# hauptplatine.net
KiCad netlist of a schematic drawn in EAGLE
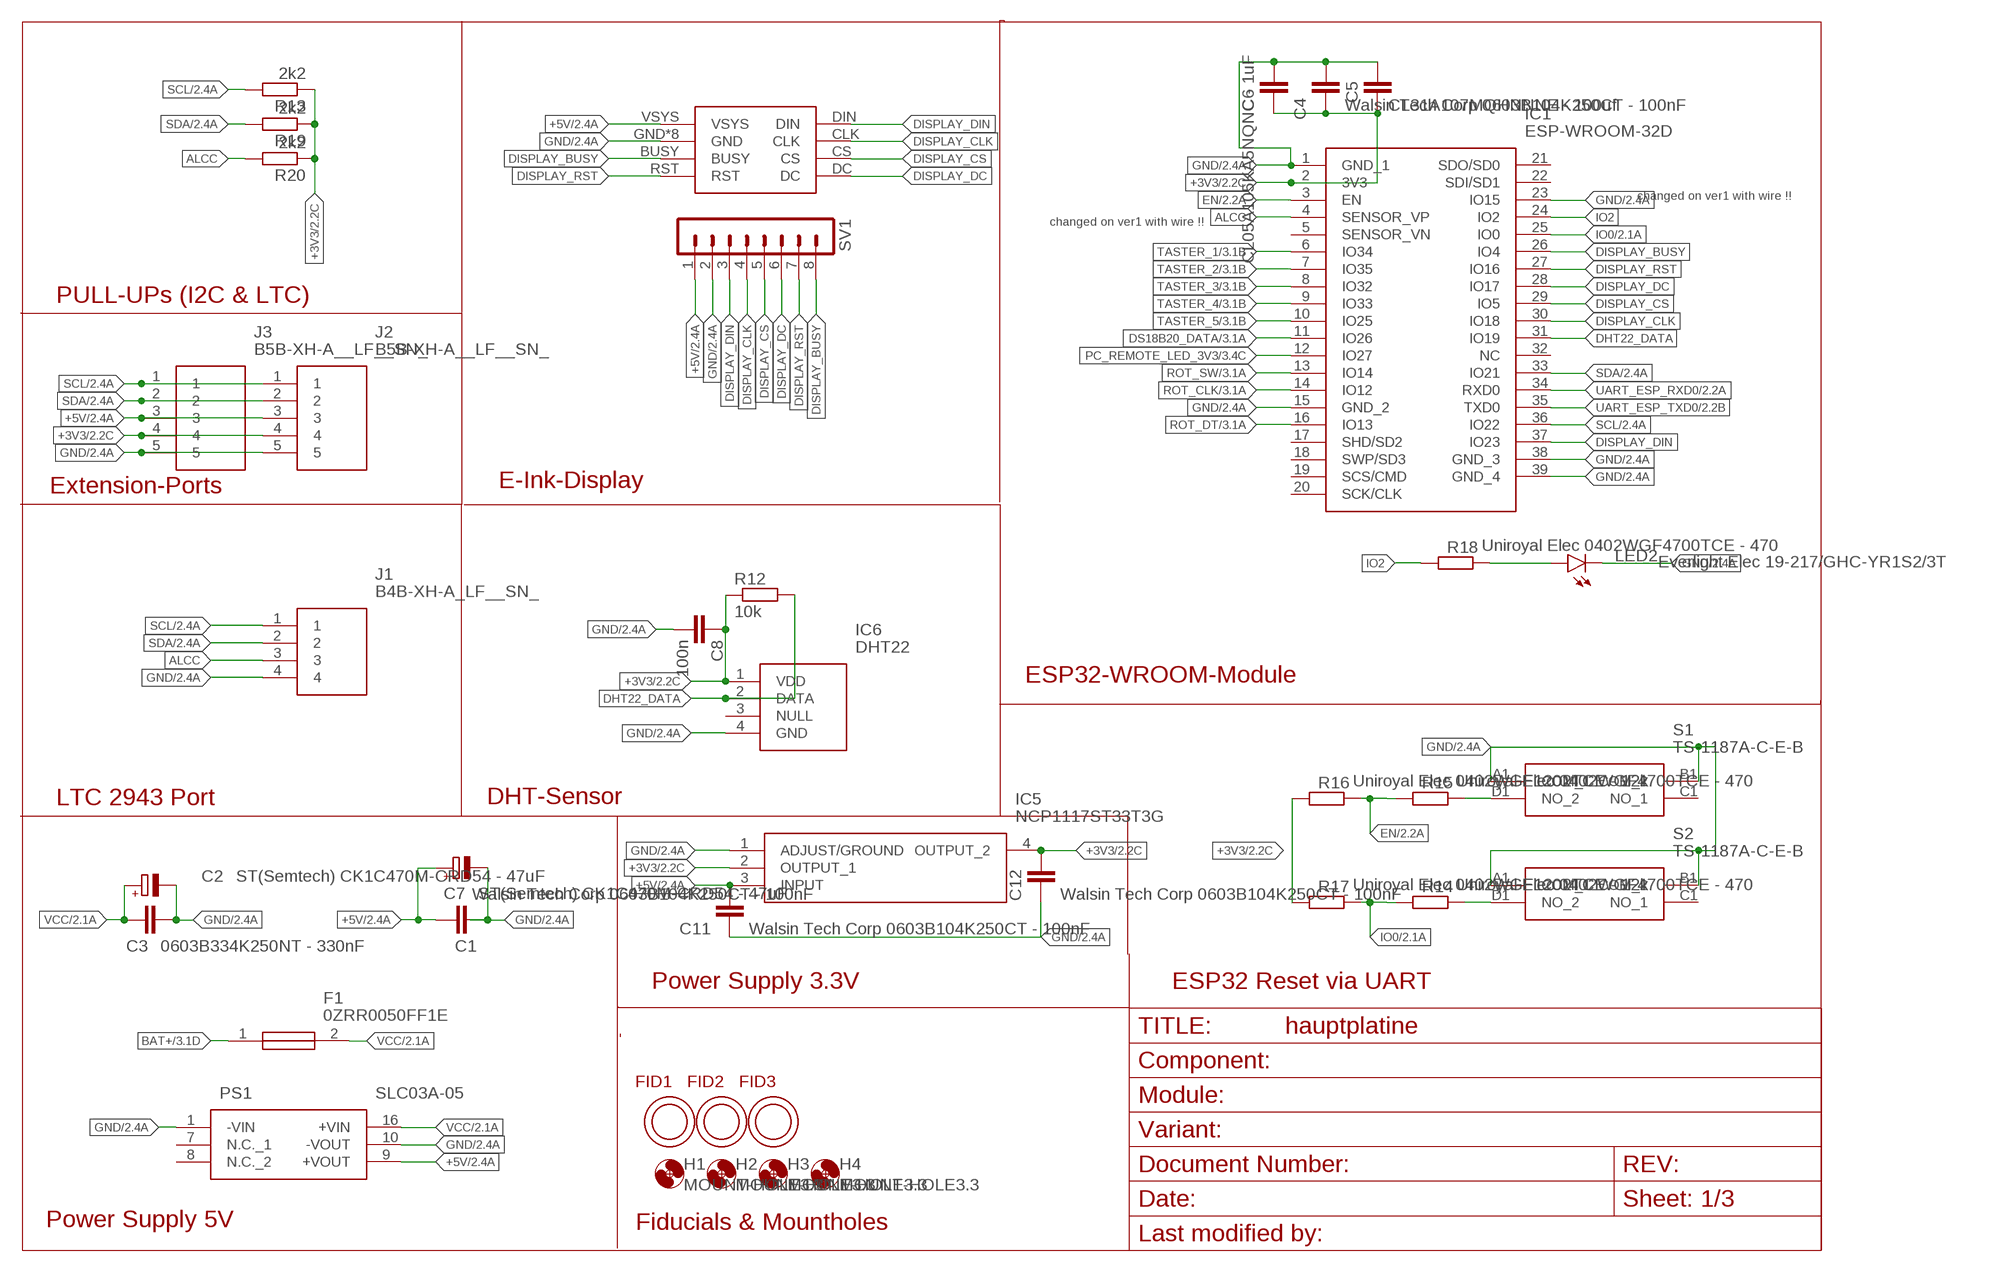
[diagram p0: schematic, sheet 1]
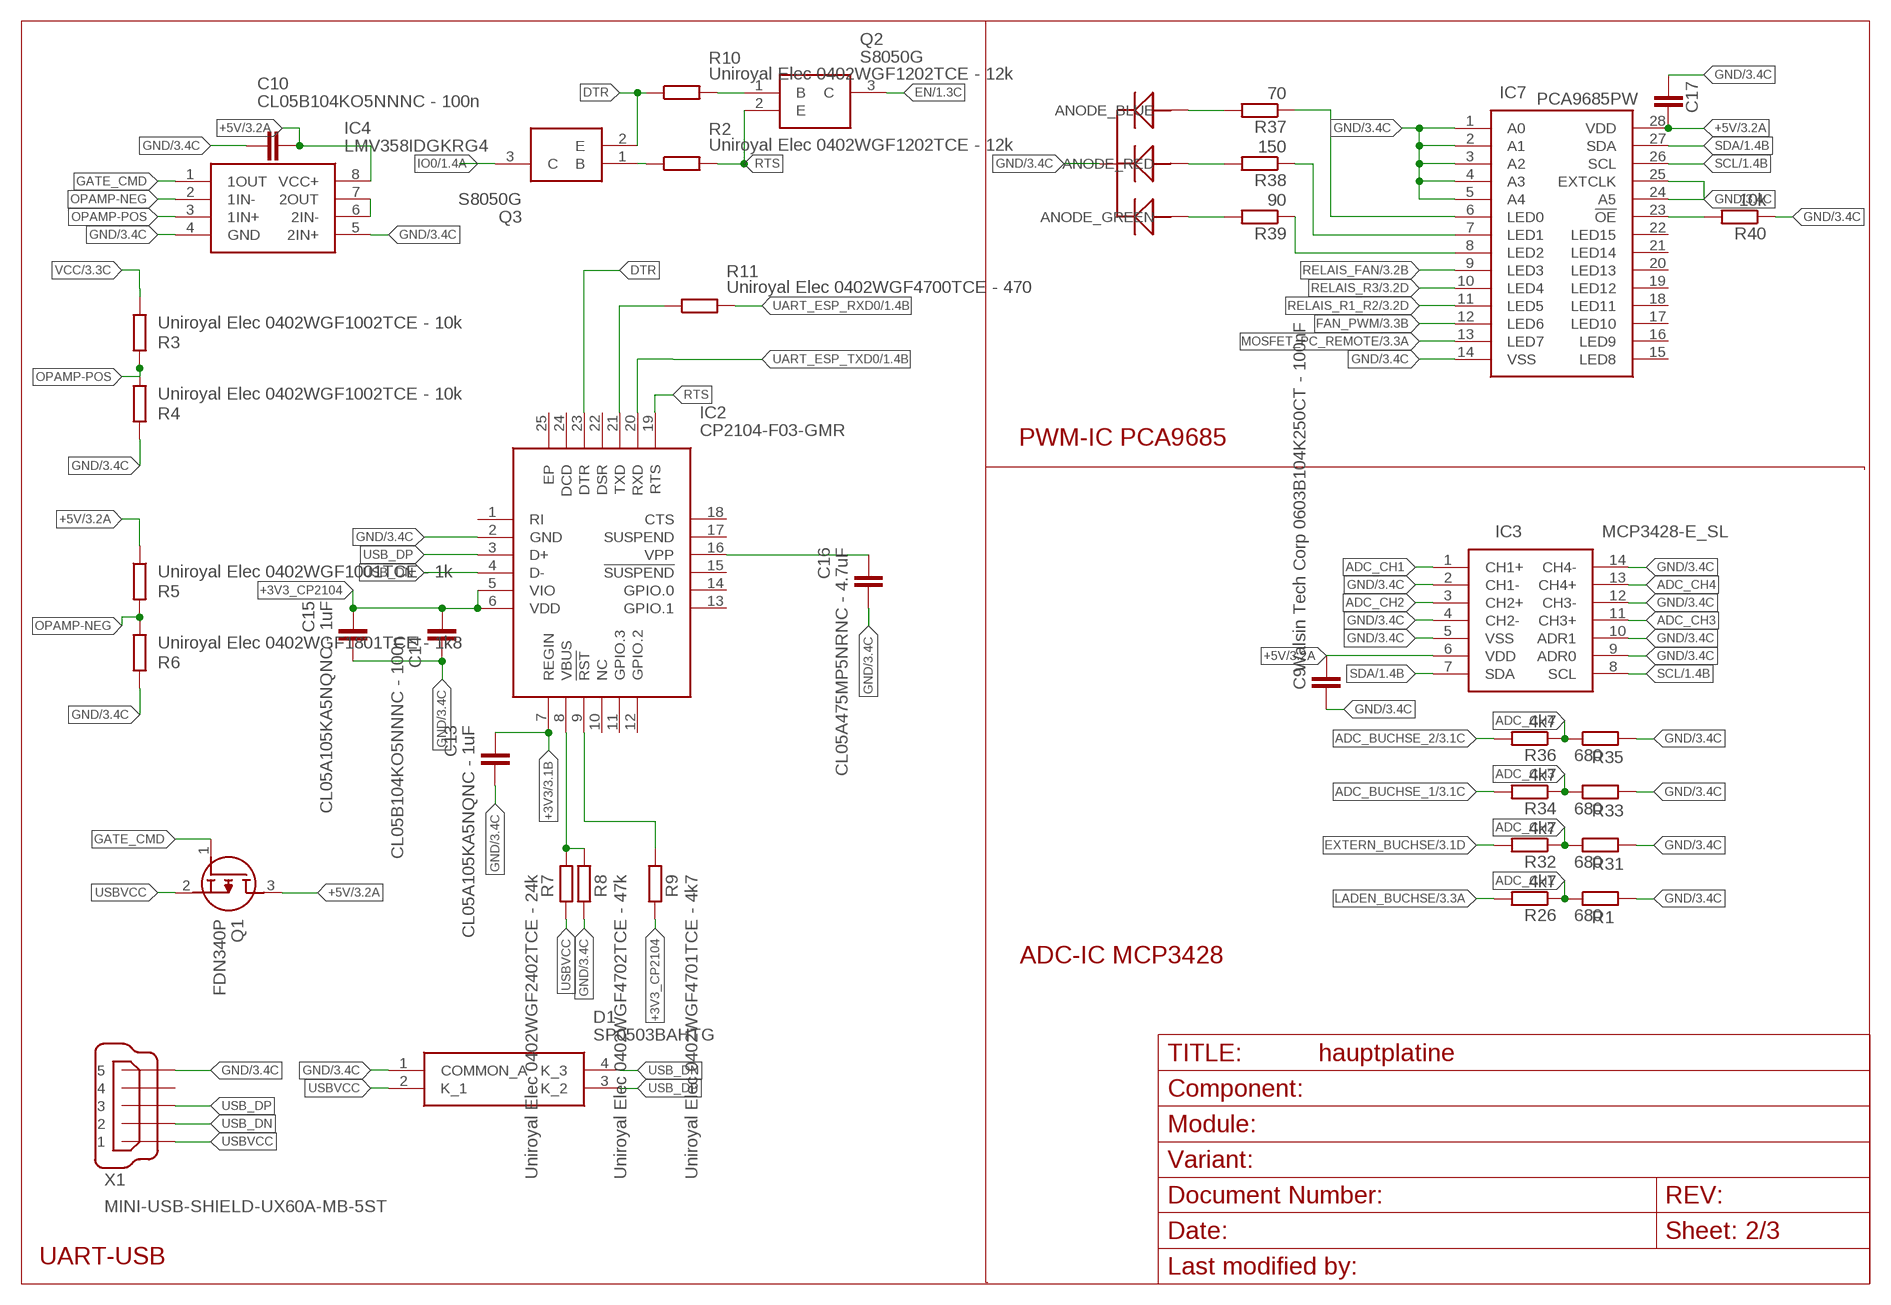
[diagram p1: schematic, sheet 2]
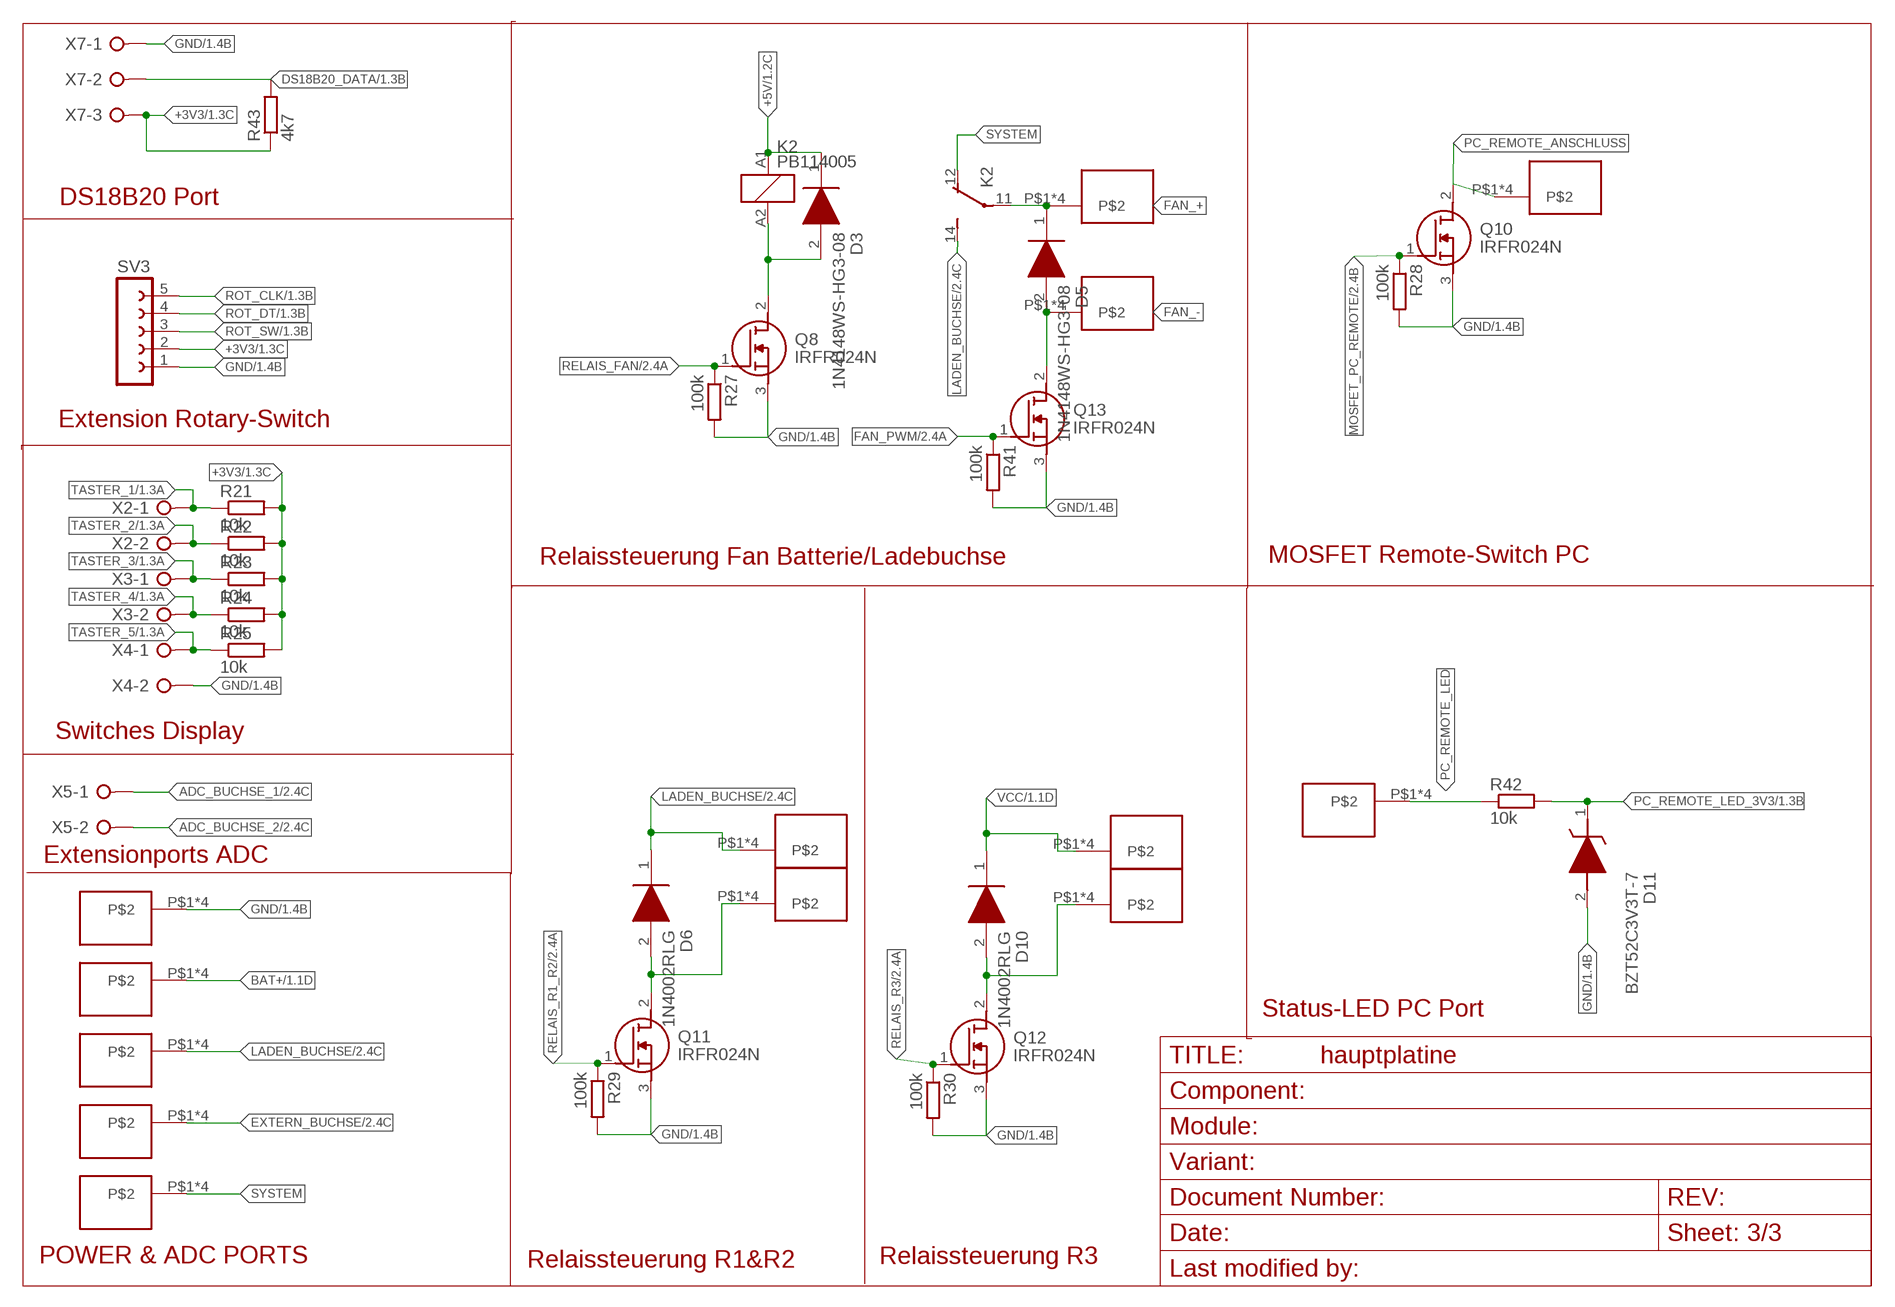
[diagram p2: schematic, sheet 3]

(export (version "E")
  (design (tool "Eeschema 10.0.6"))
  (components
    (comp (ref "C1")
      (value "Walsin Tech Corp 0603B104K250CT - 100nF")
      (footprint "eagle-import:C0603")
      (libsource (lib "eagle-import") (part "rcl_334_C-EUC0603"))
    )
    (comp (ref "C2")
      (value "ST(Semtech) CK1C470M-CRD54 - 47uF")
      (footprint "eagle-import:PANASONIC_C")
      (libsource (lib "eagle-import") (part "CPOL-EUC"))
    )
    (comp (ref "C3")
      (value "0603B334K250NT - 330nF")
      (footprint "eagle-import:C0603")
      (libsource (lib "eagle-import") (part "rcl_334_C-EUC0603"))
    )
    (comp (ref "C4")
      (value "Walsin Tech Corp 0603B104K250CT - 100nF")
      (footprint "eagle-import:C0603")
      (libsource (lib "eagle-import") (part "rcl_334_C-EUC0603"))
    )
    (comp (ref "C5")
      (value "CL31A107MQHNNNE - 100uf")
      (footprint "eagle-import:C1206")
      (libsource (lib "eagle-import") (part "rcl_334_C-EUC1206"))
    )
    (comp (ref "C6")
      (value "CL05A105KA5NQNC - 1uF")
      (footprint "eagle-import:C0402")
      (libsource (lib "eagle-import") (part "rcl_334_C-EUC0402"))
    )
    (comp (ref "C7")
      (value "ST(Semtech) CK1C470M-CRD54 - 47uF")
      (footprint "eagle-import:PANASONIC_C")
      (libsource (lib "eagle-import") (part "CPOL-EUC"))
    )
    (comp (ref "C8")
      (value "100n")
      (footprint "eagle-import:C1206")
      (libsource (lib "eagle-import") (part "C-EUC1206"))
    )
    (comp (ref "C11")
      (value "Walsin Tech Corp 0603B104K250CT - 100nF")
      (footprint "eagle-import:C0603")
      (libsource (lib "eagle-import") (part "rcl_334_C-EUC0603"))
    )
    (comp (ref "C12")
      (value "Walsin Tech Corp 0603B104K250CT - 100nF")
      (footprint "eagle-import:C0603")
      (libsource (lib "eagle-import") (part "rcl_334_C-EUC0603"))
    )
    (comp (ref "F1")
      (value "0ZRR0050FF1E")
      (footprint "eagle-import:0ZRR0050FF1E")
      (fields (field (name "MOUSER_PART_NUMBER") "530-0ZRR0050FF1E"))
      (libsource (lib "eagle-import") (part "0ZRR0050FF1E"))
    )
    (comp (ref "FID1")
      (value "OPEN-PNP-FIDUCIAL")
      (footprint "eagle-import:OPEN-PNP-FIDUCIAL")
      (libsource (lib "eagle-import") (part "OPEN-PNP-FIDUCIAL"))
    )
    (comp (ref "FID2")
      (value "OPEN-PNP-FIDUCIAL")
      (footprint "eagle-import:OPEN-PNP-FIDUCIAL")
      (libsource (lib "eagle-import") (part "OPEN-PNP-FIDUCIAL"))
    )
    (comp (ref "FID3")
      (value "OPEN-PNP-FIDUCIAL")
      (footprint "eagle-import:OPEN-PNP-FIDUCIAL")
      (libsource (lib "eagle-import") (part "OPEN-PNP-FIDUCIAL"))
    )
    (comp (ref "H1")
      (value "MOUNT-HOLE3.3")
      (footprint "eagle-import:3,3")
      (libsource (lib "eagle-import") (part "MOUNT-HOLE3.3"))
    )
    (comp (ref "H2")
      (value "MOUNT-HOLE3.3")
      (footprint "eagle-import:3,3")
      (libsource (lib "eagle-import") (part "MOUNT-HOLE3.3"))
    )
    (comp (ref "H3")
      (value "MOUNT-HOLE3.3")
      (footprint "eagle-import:3,3")
      (libsource (lib "eagle-import") (part "MOUNT-HOLE3.3"))
    )
    (comp (ref "H4")
      (value "MOUNT-HOLE3.3")
      (footprint "eagle-import:3,3")
      (libsource (lib "eagle-import") (part "MOUNT-HOLE3.3"))
    )
    (comp (ref "IC1")
      (value "ESP-WROOM-32D")
      (footprint "eagle-import:ESPWROOM32D")
      (fields (field (name "MOUSER_PART_NUMBER") "356-ESP-WROOM-32D"))
      (libsource (lib "eagle-import") (part "ESP-WROOM-32D"))
    )
    (comp (ref "IC5")
      (value "NCP1117ST33T3G")
      (footprint "eagle-import:SOT230P700X180-4N")
      (fields (field (name "MOUSER_PART_NUMBER") "863-NCP1117ST33T3G"))
      (libsource (lib "eagle-import") (part "NCP1117ST33T3G"))
    )
    (comp (ref "IC6")
      (value "DHT22")
      (footprint "eagle-import:DHT22")
      (libsource (lib "eagle-import") (part "DHT22"))
    )
    (comp (ref "J1")
      (value "B4B-XH-A_LF__SN_")
      (footprint "eagle-import:B4BXHALFSN")
      (fields (field (name "ARROW_PART_NUMBER") "B4B-XH-A(LF)(SN)"))
      (libsource (lib "eagle-import") (part "B4B-XH-A_LF__SN_"))
    )
    (comp (ref "J2")
      (value "B5B-XH-A__LF__SN_")
      (footprint "eagle-import:SHDR5W64P0X250_1X5_1490X575X70")
      (fields (field (name "MANUFACTURER_PART_NUMBER") "B5B-XH-A (LF)(SN)"))
      (libsource (lib "eagle-import") (part "B5B-XH-A__LF__SN_"))
    )
    (comp (ref "J3")
      (value "B5B-XH-A__LF__SN_")
      (footprint "eagle-import:SHDR5W64P0X250_1X5_1490X575X70")
      (fields (field (name "MANUFACTURER_PART_NUMBER") "B5B-XH-A (LF)(SN)"))
      (libsource (lib "eagle-import") (part "B5B-XH-A__LF__SN_"))
    )
    (comp (ref "LED2")
      (value "Everlight Elec 19-217/GHC-YR1S2/3T")
      (footprint "eagle-import:CHIPLED_0603")
      (libsource (lib "eagle-import") (part "LEDCHIPLED_0603"))
    )
    (comp (ref "PS1")
      (value "SLC03A-05")
      (footprint "eagle-import:SLC03A05")
      (fields (field (name "MOUSER_PART_NUMBER") "709-SLC03A-05"))
      (libsource (lib "eagle-import") (part "SLC03A-05"))
    )
    (comp (ref "R12")
      (value "10k")
      (footprint "eagle-import:R1206")
      (libsource (lib "eagle-import") (part "R-EU_R1206"))
    )
    (comp (ref "R13")
      (value "2k2")
      (footprint "eagle-import:R1206")
      (libsource (lib "eagle-import") (part "R-EU_R1206"))
    )
    (comp (ref "R14")
      (value "Uniroyal Elec 0402WGF4700TCE - 470")
      (footprint "eagle-import:R0402")
      (libsource (lib "eagle-import") (part "rcl_334_R-EU_R0402"))
    )
    (comp (ref "R15")
      (value "Uniroyal Elec 0402WGF4700TCE - 470")
      (footprint "eagle-import:R0402")
      (libsource (lib "eagle-import") (part "rcl_334_R-EU_R0402"))
    )
    (comp (ref "R16")
      (value "Uniroyal Elec 0402WGF1202TCE - 12k")
      (footprint "eagle-import:R0402")
      (libsource (lib "eagle-import") (part "rcl_334_R-EU_R0402"))
    )
    (comp (ref "R17")
      (value "Uniroyal Elec 0402WGF1202TCE - 12k")
      (footprint "eagle-import:R0402")
      (libsource (lib "eagle-import") (part "rcl_334_R-EU_R0402"))
    )
    (comp (ref "R18")
      (value "Uniroyal Elec 0402WGF4700TCE - 470")
      (footprint "eagle-import:R0402")
      (libsource (lib "eagle-import") (part "rcl_334_R-EU_R0402"))
    )
    (comp (ref "R19")
      (value "2k2")
      (footprint "eagle-import:R1206")
      (libsource (lib "eagle-import") (part "R-EU_R1206"))
    )
    (comp (ref "R20")
      (value "2k2")
      (footprint "eagle-import:R1206")
      (libsource (lib "eagle-import") (part "R-EU_R1206"))
    )
    (comp (ref "S1")
      (value "TS-1187A-C-E-B")
      (footprint "eagle-import:TS1187ACEB")
      (fields (field (name "MOUSER_PART_NUMBER") "611-PTS526SK15SMR2L"))
      (libsource (lib "eagle-import") (part "TS-1187A-C-E-B"))
    )
    (comp (ref "S2")
      (value "TS-1187A-C-E-B")
      (footprint "eagle-import:TS1187ACEB")
      (fields (field (name "MOUSER_PART_NUMBER") "611-PTS526SK15SMR2L"))
      (libsource (lib "eagle-import") (part "TS-1187A-C-E-B"))
    )
    (comp (ref "SV1")
      (value "MA08-1")
      (footprint "eagle-import:MA08-1")
      (libsource (lib "eagle-import") (part "MA08-1"))
    )
    (comp (ref "U$1")
      (value "PICO-EPAPER-2.9-V3")
      (footprint "eagle-import:PICO-EPAPER-2.9-V3")
      (libsource (lib "eagle-import") (part "PICO-EPAPER-2.9-V3"))
    )
    (comp (ref "C9")
      (value "Walsin Tech Corp 0603B104K250CT - 100nF")
      (footprint "eagle-import:C0603")
      (libsource (lib "eagle-import") (part "rcl_334_C-EUC0603"))
    )
    (comp (ref "C10")
      (value "CL05B104KO5NNNC - 100n")
      (footprint "eagle-import:C0402")
      (libsource (lib "eagle-import") (part "rcl_334_C-EUC0402"))
    )
    (comp (ref "C13")
      (value "CL05A105KA5NQNC - 1uF")
      (footprint "eagle-import:C0402")
      (libsource (lib "eagle-import") (part "rcl_334_C-EUC0402"))
    )
    (comp (ref "C14")
      (value "CL05B104KO5NNNC - 100n")
      (footprint "eagle-import:C0402")
      (libsource (lib "eagle-import") (part "rcl_334_C-EUC0402"))
    )
    (comp (ref "C15")
      (value "CL05A105KA5NQNC - 1uF")
      (footprint "eagle-import:C0402")
      (libsource (lib "eagle-import") (part "rcl_334_C-EUC0402"))
    )
    (comp (ref "C16")
      (value "CL05A475MP5NRNC - 4.7uF")
      (footprint "eagle-import:C0402")
      (libsource (lib "eagle-import") (part "rcl_334_C-EUC0402"))
    )
    (comp (ref "C17")
      (value "Walsin Tech Corp 0603B104K250CT - 100nF")
      (footprint "eagle-import:C0603")
      (libsource (lib "eagle-import") (part "rcl_334_C-EUC0603"))
    )
    (comp (ref "D1")
      (value "SP0503BAHTG")
      (footprint "eagle-import:SP0503BAHTG")
      (fields (field (name "MOUSER_PART_NUMBER") "576-SP0503BAHTG"))
      (libsource (lib "eagle-import") (part "SP0503BAHTG"))
    )
    (comp (ref "IC2")
      (value "CP2104-F03-GMR")
      (footprint "eagle-import:QFN50P400X400X80-25N")
      (fields (field (name "MOUSER_PART_NUMBER") "634-CP2104-F03-GMR"))
      (libsource (lib "eagle-import") (part "CP2104-F03-GMR"))
    )
    (comp (ref "IC3")
      (value "MCP3428-E_SL")
      (footprint "eagle-import:SOIC127P600X175-14N")
      (fields
        (field (name "ARROW_PART_NUMBER") "MCP3428-E/SL")
        (field (name "MOUSER_PART_NUMBER") "579-MCP3428E/SL")
      )
      (libsource (lib "eagle-import") (part "MCP3428-E_SL"))
    )
    (comp (ref "IC4")
      (value "LMV358IDGKRG4")
      (footprint "eagle-import:SOP65P490X110-8N")
      (fields (field (name "MOUSER_PART_NUMBER") "595-LMV358IDGKRG4"))
      (libsource (lib "eagle-import") (part "LMV358IDGKRG4"))
    )
    (comp (ref "IC7")
      (value "PCA9685PW")
      (footprint "eagle-import:SOP65P640X110-28N")
      (libsource (lib "eagle-import") (part "PCA9685PW"))
    )
    (comp (ref "Q1")
      (value "FDN340P")
      (footprint "eagle-import:SOT95P237X112-3N")
      (fields (field (name "MOUSER_PART_NUMBER") "512-FDN340P"))
      (libsource (lib "eagle-import") (part "FDN340P"))
    )
    (comp (ref "Q2")
      (value "S8050G")
      (footprint "eagle-import:SOT95P240X110-3N")
      (libsource (lib "eagle-import") (part "S8050G"))
    )
    (comp (ref "Q3")
      (value "S8050G")
      (footprint "eagle-import:SOT95P240X110-3N")
      (libsource (lib "eagle-import") (part "S8050G"))
    )
    (comp (ref "R1")
      (value "680")
      (footprint "eagle-import:R1206")
      (libsource (lib "eagle-import") (part "R-EU_R1206"))
    )
    (comp (ref "R2")
      (value "Uniroyal Elec 0402WGF1202TCE - 12k")
      (footprint "eagle-import:R0402")
      (libsource (lib "eagle-import") (part "rcl_334_R-EU_R0402"))
    )
    (comp (ref "R3")
      (value "Uniroyal Elec 0402WGF1002TCE - 10k")
      (footprint "eagle-import:R0402")
      (libsource (lib "eagle-import") (part "rcl_334_R-EU_R0402"))
    )
    (comp (ref "R4")
      (value "Uniroyal Elec 0402WGF1002TCE - 10k")
      (footprint "eagle-import:R0402")
      (libsource (lib "eagle-import") (part "rcl_334_R-EU_R0402"))
    )
    (comp (ref "R5")
      (value "Uniroyal Elec 0402WGF1001TCE - 1k")
      (footprint "eagle-import:R0402")
      (libsource (lib "eagle-import") (part "rcl_334_R-EU_R0402"))
    )
    (comp (ref "R6")
      (value "Uniroyal Elec 0402WGF1801TCE - 1k8")
      (footprint "eagle-import:R0402")
      (libsource (lib "eagle-import") (part "rcl_334_R-EU_R0402"))
    )
    (comp (ref "R7")
      (value "Uniroyal Elec 0402WGF2402TCE - 24k")
      (footprint "eagle-import:R0402")
      (libsource (lib "eagle-import") (part "rcl_334_R-EU_R0402"))
    )
    (comp (ref "R8")
      (value "Uniroyal Elec 0402WGF4702TCE - 47k")
      (footprint "eagle-import:R0402")
      (libsource (lib "eagle-import") (part "rcl_334_R-EU_R0402"))
    )
    (comp (ref "R9")
      (value "Uniroyal Elec 0402WGF4701TCE - 4k7")
      (footprint "eagle-import:R0402")
      (libsource (lib "eagle-import") (part "rcl_334_R-EU_R0402"))
    )
    (comp (ref "R10")
      (value "Uniroyal Elec 0402WGF1202TCE - 12k")
      (footprint "eagle-import:R0402")
      (libsource (lib "eagle-import") (part "rcl_334_R-EU_R0402"))
    )
    (comp (ref "R11")
      (value "Uniroyal Elec 0402WGF4700TCE - 470")
      (footprint "eagle-import:R0402")
      (libsource (lib "eagle-import") (part "rcl_334_R-EU_R0402"))
    )
    (comp (ref "R26")
      (value "4k7")
      (footprint "eagle-import:R1206")
      (libsource (lib "eagle-import") (part "R-EU_R1206"))
    )
    (comp (ref "R31")
      (value "680")
      (footprint "eagle-import:R1206")
      (libsource (lib "eagle-import") (part "R-EU_R1206"))
    )
    (comp (ref "R32")
      (value "4k7")
      (footprint "eagle-import:R1206")
      (libsource (lib "eagle-import") (part "R-EU_R1206"))
    )
    (comp (ref "R33")
      (value "680")
      (footprint "eagle-import:R1206")
      (libsource (lib "eagle-import") (part "R-EU_R1206"))
    )
    (comp (ref "R34")
      (value "4k7")
      (footprint "eagle-import:R1206")
      (libsource (lib "eagle-import") (part "R-EU_R1206"))
    )
    (comp (ref "R35")
      (value "680")
      (footprint "eagle-import:R1206")
      (libsource (lib "eagle-import") (part "R-EU_R1206"))
    )
    (comp (ref "R36")
      (value "4k7")
      (footprint "eagle-import:R1206")
      (libsource (lib "eagle-import") (part "R-EU_R1206"))
    )
    (comp (ref "R37")
      (value "70")
      (footprint "eagle-import:R1206")
      (libsource (lib "eagle-import") (part "R-EU_R1206"))
    )
    (comp (ref "R38")
      (value "150")
      (footprint "eagle-import:R1206")
      (libsource (lib "eagle-import") (part "R-EU_R1206"))
    )
    (comp (ref "R39")
      (value "90")
      (footprint "eagle-import:R1206")
      (libsource (lib "eagle-import") (part "R-EU_R1206"))
    )
    (comp (ref "R40")
      (value "10k")
      (footprint "eagle-import:R1206")
      (libsource (lib "eagle-import") (part "R-EU_R1206"))
    )
    (comp (ref "U$12")
      (value "RG_LED_5MM")
      (footprint "eagle-import:RGB_LED_5MM")
      (libsource (lib "eagle-import") (part "RG_LED_5MM"))
    )
    (comp (ref "X1")
      (value "MINI-USB-SHIELD-UX60A-MB-5ST")
      (footprint "eagle-import:UX60A-MB-5ST")
      (libsource (lib "eagle-import") (part "MINI-USB-SHIELD-UX60A-MB-5ST"))
    )
    (comp (ref "D3")
      (value "1N4148WS-HG3-08")
      (footprint "eagle-import:SOD2713X115N")
      (fields (field (name "MOUSER_PART_NUMBER") "78-1N4148WS-HG3-08"))
      (libsource (lib "eagle-import") (part "1N4148WS-HG3-08"))
    )
    (comp (ref "D5")
      (value "1N4148WS-HG3-08")
      (footprint "eagle-import:SOD2713X115N")
      (fields (field (name "MOUSER_PART_NUMBER") "78-1N4148WS-HG3-08"))
      (libsource (lib "eagle-import") (part "1N4148WS-HG3-08"))
    )
    (comp (ref "D6")
      (value "1N4002RLG")
      (footprint "eagle-import:DIOAD1405W86L465D235")
      (fields (field (name "MOUSER_PART_NUMBER") "863-1N4002RLG"))
      (libsource (lib "eagle-import") (part "1N4002RLG"))
    )
    (comp (ref "D10")
      (value "1N4002RLG")
      (footprint "eagle-import:DIOAD1405W86L465D235")
      (fields (field (name "MOUSER_PART_NUMBER") "863-1N4002RLG"))
      (libsource (lib "eagle-import") (part "1N4002RLG"))
    )
    (comp (ref "D11")
      (value "BZT52C3V3T-7")
      (footprint "eagle-import:SODFL1608X65N")
      (fields (field (name "MOUSER_PART_NUMBER") "621-BZT52C3V3T-7"))
      (libsource (lib "eagle-import") (part "BZT52C3V3T-7"))
    )
    (comp (ref "K2")
      (value "PB114005")
      (footprint "eagle-import:PB")
      (fields (field (name "MF") "TYCO ELECTRONICS") (field (name "MPN") "PB114006"))
      (libsource (lib "eagle-import") (part "PB?141006"))
    )
    (comp (ref "Q8")
      (value "IRFR024N")
      (footprint "eagle-import:IRFR024TRPBFBE3")
      (fields
        (field (name "ARROW_PART_NUMBER") "IRFR024TRPBF-BE3")
        (field (name "MOUSER_PART_NUMBER") "78-IRFR024TRPBF-BE3")
      )
      (libsource (lib "eagle-import") (part "IRFR024TRPBF-BE3"))
    )
    (comp (ref "Q10")
      (value "IRFR024N")
      (footprint "eagle-import:IRFR024TRPBFBE3")
      (fields
        (field (name "ARROW_PART_NUMBER") "IRFR024TRPBF-BE3")
        (field (name "MOUSER_PART_NUMBER") "78-IRFR024TRPBF-BE3")
      )
      (libsource (lib "eagle-import") (part "IRFR024TRPBF-BE3"))
    )
    (comp (ref "Q11")
      (value "IRFR024N")
      (footprint "eagle-import:IRFR024TRPBFBE3")
      (fields
        (field (name "ARROW_PART_NUMBER") "IRFR024TRPBF-BE3")
        (field (name "MOUSER_PART_NUMBER") "78-IRFR024TRPBF-BE3")
      )
      (libsource (lib "eagle-import") (part "IRFR024TRPBF-BE3"))
    )
    (comp (ref "Q12")
      (value "IRFR024N")
      (footprint "eagle-import:IRFR024TRPBFBE3")
      (fields
        (field (name "ARROW_PART_NUMBER") "IRFR024TRPBF-BE3")
        (field (name "MOUSER_PART_NUMBER") "78-IRFR024TRPBF-BE3")
      )
      (libsource (lib "eagle-import") (part "IRFR024TRPBF-BE3"))
    )
    (comp (ref "Q13")
      (value "IRFR024N")
      (footprint "eagle-import:IRFR024TRPBFBE3")
      (fields
        (field (name "ARROW_PART_NUMBER") "IRFR024TRPBF-BE3")
        (field (name "MOUSER_PART_NUMBER") "78-IRFR024TRPBF-BE3")
      )
      (libsource (lib "eagle-import") (part "IRFR024TRPBF-BE3"))
    )
    (comp (ref "R21")
      (value "10k")
      (footprint "eagle-import:R0805")
      (libsource (lib "eagle-import") (part "R-EU_R0805"))
    )
    (comp (ref "R22")
      (value "10k")
      (footprint "eagle-import:R0805")
      (libsource (lib "eagle-import") (part "R-EU_R0805"))
    )
    (comp (ref "R23")
      (value "10k")
      (footprint "eagle-import:R0805")
      (libsource (lib "eagle-import") (part "R-EU_R0805"))
    )
    (comp (ref "R24")
      (value "10k")
      (footprint "eagle-import:R0805")
      (libsource (lib "eagle-import") (part "R-EU_R0805"))
    )
    (comp (ref "R25")
      (value "10k")
      (footprint "eagle-import:R0805")
      (libsource (lib "eagle-import") (part "R-EU_R0805"))
    )
    (comp (ref "R27")
      (value "100k")
      (footprint "eagle-import:R1206")
      (libsource (lib "eagle-import") (part "R-EU_R1206"))
    )
    (comp (ref "R28")
      (value "100k")
      (footprint "eagle-import:R1206")
      (libsource (lib "eagle-import") (part "R-EU_R1206"))
    )
    (comp (ref "R29")
      (value "100k")
      (footprint "eagle-import:R1206")
      (libsource (lib "eagle-import") (part "R-EU_R1206"))
    )
    (comp (ref "R30")
      (value "100k")
      (footprint "eagle-import:R1206")
      (libsource (lib "eagle-import") (part "R-EU_R1206"))
    )
    (comp (ref "R41")
      (value "100k")
      (footprint "eagle-import:R1206")
      (libsource (lib "eagle-import") (part "R-EU_R1206"))
    )
    (comp (ref "R42")
      (value "10k")
      (footprint "eagle-import:R1206")
      (libsource (lib "eagle-import") (part "R-EU_R1206"))
    )
    (comp (ref "R43")
      (value "4k7")
      (footprint "eagle-import:R0805")
      (libsource (lib "eagle-import") (part "R-EU_R0805"))
    )
    (comp (ref "SV3")
      (value "FE05-1")
      (footprint "eagle-import:FE05-1")
      (libsource (lib "eagle-import") (part "FE05-1"))
    )
    (comp (ref "U$2")
      (value "WE-REDCUBE-74650173")
      (footprint "eagle-import:WE-REDCUBE-74650173")
      (libsource (lib "eagle-import") (part "WE-REDCUBE-74650173"))
    )
    (comp (ref "U$17")
      (value "WE-REDCUBE-74650173")
      (footprint "eagle-import:WE-REDCUBE-74650173")
      (libsource (lib "eagle-import") (part "WE-REDCUBE-74650173"))
    )
    (comp (ref "U$18")
      (value "WE-REDCUBE-74650173")
      (footprint "eagle-import:WE-REDCUBE-74650173")
      (libsource (lib "eagle-import") (part "WE-REDCUBE-74650173"))
    )
    (comp (ref "U$19")
      (value "WE-REDCUBE-74650173")
      (footprint "eagle-import:WE-REDCUBE-74650173")
      (libsource (lib "eagle-import") (part "WE-REDCUBE-74650173"))
    )
    (comp (ref "U$20")
      (value "WE-REDCUBE-74650173")
      (footprint "eagle-import:WE-REDCUBE-74650173")
      (libsource (lib "eagle-import") (part "WE-REDCUBE-74650173"))
    )
    (comp (ref "U$21")
      (value "WE-REDCUBE-74650173")
      (footprint "eagle-import:WE-REDCUBE-74650173")
      (libsource (lib "eagle-import") (part "WE-REDCUBE-74650173"))
    )
    (comp (ref "U$22")
      (value "WE-REDCUBE-74650173")
      (footprint "eagle-import:WE-REDCUBE-74650173")
      (libsource (lib "eagle-import") (part "WE-REDCUBE-74650173"))
    )
    (comp (ref "U$23")
      (value "WE-REDCUBE-74650173")
      (footprint "eagle-import:WE-REDCUBE-74650173")
      (libsource (lib "eagle-import") (part "WE-REDCUBE-74650173"))
    )
    (comp (ref "U$24")
      (value "WE-REDCUBE-74650173")
      (footprint "eagle-import:WE-REDCUBE-74650173")
      (libsource (lib "eagle-import") (part "WE-REDCUBE-74650173"))
    )
    (comp (ref "U$25")
      (value "WE-REDCUBE-74650173")
      (footprint "eagle-import:WE-REDCUBE-74650173")
      (libsource (lib "eagle-import") (part "WE-REDCUBE-74650173"))
    )
    (comp (ref "U$26")
      (value "WE-REDCUBE-74650173")
      (footprint "eagle-import:WE-REDCUBE-74650173")
      (libsource (lib "eagle-import") (part "WE-REDCUBE-74650173"))
    )
    (comp (ref "U$27")
      (value "WE-REDCUBE-74650173")
      (footprint "eagle-import:WE-REDCUBE-74650173")
      (libsource (lib "eagle-import") (part "WE-REDCUBE-74650173"))
    )
    (comp (ref "U$28")
      (value "WE-REDCUBE-74650173")
      (footprint "eagle-import:WE-REDCUBE-74650173")
      (libsource (lib "eagle-import") (part "WE-REDCUBE-74650173"))
    )
    (comp (ref "X2")
      (value "W237-02P")
      (footprint "eagle-import:W237-132")
      (libsource (lib "eagle-import") (part "W237-02P"))
    )
    (comp (ref "X3")
      (value "W237-02P")
      (footprint "eagle-import:W237-132")
      (libsource (lib "eagle-import") (part "W237-02P"))
    )
    (comp (ref "X4")
      (value "W237-02P")
      (footprint "eagle-import:W237-132")
      (libsource (lib "eagle-import") (part "W237-02P"))
    )
    (comp (ref "X5")
      (value "W237-02P")
      (footprint "eagle-import:W237-132")
      (libsource (lib "eagle-import") (part "W237-02P"))
    )
    (comp (ref "X7")
      (value "W237-3E")
      (footprint "eagle-import:W237-3E")
      (libsource (lib "eagle-import") (part "W237-3E"))
    )
  )
  (nets
    (net (code "1") (name "+3V3") (class "Default")
      (node (ref "C12") (pin "2") (pinfunction "2_2") (pintype "passive"))
      (node (ref "C13") (pin "2") (pinfunction "2_2") (pintype "passive"))
      (node (ref "C4") (pin "1") (pinfunction "1_1") (pintype "passive"))
      (node (ref "C5") (pin "2") (pinfunction "2_2") (pintype "passive"))
      (node (ref "C6") (pin "1") (pinfunction "1_1") (pintype "passive"))
      (node (ref "C8") (pin "1") (pinfunction "1_1") (pintype "passive"))
      (node (ref "IC1") (pin "2") (pinfunction "3V3_2") (pintype "bidirectional"))
      (node (ref "IC2") (pin "7") (pinfunction "REGIN_7") (pintype "bidirectional"))
      (node (ref "IC5") (pin "2") (pinfunction "OUTPUT_1_2") (pintype "bidirectional"))
      (node (ref "IC5") (pin "4") (pinfunction "OUTPUT_2_4") (pintype "bidirectional"))
      (node (ref "IC6") (pin "1") (pinfunction "VDD_1") (pintype "bidirectional"))
      (node (ref "J2") (pin "4") (pinfunction "4_4") (pintype "bidirectional"))
      (node (ref "J3") (pin "4") (pinfunction "4_4") (pintype "bidirectional"))
      (node (ref "R12") (pin "1") (pinfunction "1_1") (pintype "passive"))
      (node (ref "R13") (pin "1") (pinfunction "1_1") (pintype "passive"))
      (node (ref "R16") (pin "1") (pinfunction "1_1") (pintype "passive"))
      (node (ref "R17") (pin "1") (pinfunction "1_1") (pintype "passive"))
      (node (ref "R19") (pin "1") (pinfunction "1_1") (pintype "passive"))
      (node (ref "R20") (pin "1") (pinfunction "1_1") (pintype "passive"))
      (node (ref "R21") (pin "2") (pinfunction "2_2") (pintype "passive"))
      (node (ref "R22") (pin "2") (pinfunction "2_2") (pintype "passive"))
      (node (ref "R23") (pin "2") (pinfunction "2_2") (pintype "passive"))
      (node (ref "R24") (pin "2") (pinfunction "2_2") (pintype "passive"))
      (node (ref "R25") (pin "2") (pinfunction "2_2") (pintype "passive"))
      (node (ref "R43") (pin "1") (pinfunction "1_1") (pintype "passive"))
      (node (ref "SV3") (pin "2") (pinfunction "2_2") (pintype "passive"))
      (node (ref "X7") (pin "3") (pinfunction "KL_3") (pintype "passive"))
    )
    (net (code "2") (name "+3V3_CP2104") (class "Default")
      (node (ref "C14") (pin "2") (pinfunction "2_2") (pintype "passive"))
      (node (ref "C15") (pin "2") (pinfunction "2_2") (pintype "passive"))
      (node (ref "IC2") (pin "5") (pinfunction "VIO_5") (pintype "bidirectional"))
      (node (ref "IC2") (pin "6") (pinfunction "VDD_6") (pintype "bidirectional"))
      (node (ref "R9") (pin "2") (pinfunction "2_2") (pintype "passive"))
    )
    (net (code "3") (name "+5V") (class "Default")
      (node (ref "C1") (pin "1") (pinfunction "1_1") (pintype "passive"))
      (node (ref "C10") (pin "2") (pinfunction "2_2") (pintype "passive"))
      (node (ref "C11") (pin "2") (pinfunction "2_2") (pintype "passive"))
      (node (ref "C17") (pin "1") (pinfunction "1_1") (pintype "passive"))
      (node (ref "C7") (pin "+") (pinfunction "+_+") (pintype "passive"))
      (node (ref "C9") (pin "2") (pinfunction "2_2") (pintype "passive"))
      (node (ref "D3") (pin "1") (pinfunction "K_1") (pintype "bidirectional"))
      (node (ref "IC3") (pin "6") (pinfunction "VDD_6") (pintype "bidirectional"))
      (node (ref "IC4") (pin "8") (pinfunction "VCC+_8") (pintype "bidirectional"))
      (node (ref "IC5") (pin "3") (pinfunction "INPUT_3") (pintype "bidirectional"))
      (node (ref "IC7") (pin "28") (pinfunction "VDD_28") (pintype "bidirectional"))
      (node (ref "J2") (pin "3") (pinfunction "3_3") (pintype "bidirectional"))
      (node (ref "J3") (pin "3") (pinfunction "3_3") (pintype "bidirectional"))
      (node (ref "K2") (pin "A1") (pinfunction "1_A1") (pintype "passive"))
      (node (ref "PS1") (pin "9") (pinfunction "+VOUT_9") (pintype "bidirectional"))
      (node (ref "Q1") (pin "3") (pinfunction "D_3") (pintype "bidirectional"))
      (node (ref "R5") (pin "1") (pinfunction "1_1") (pintype "passive"))
      (node (ref "SV1") (pin "1") (pinfunction "1_1") (pintype "passive"))
      (node (ref "U$1") (pin "VSYS") (pinfunction "VSYS_VSYS") (pintype "bidirectional"))
    )
    (net (code "4") (name "ADC_BUCHSE_1") (class "Default")
      (node (ref "R34") (pin "2") (pinfunction "2_2") (pintype "passive"))
      (node (ref "X5") (pin "1") (pinfunction "KL_1") (pintype "passive"))
    )
    (net (code "5") (name "ADC_BUCHSE_2") (class "Default")
      (node (ref "R36") (pin "2") (pinfunction "2_2") (pintype "passive"))
      (node (ref "X5") (pin "2") (pinfunction "KL_2") (pintype "passive"))
    )
    (net (code "6") (name "ADC_CH1") (class "Default")
      (node (ref "IC3") (pin "1") (pinfunction "CH1+_1") (pintype "bidirectional"))
      (node (ref "R1") (pin "1") (pinfunction "1_1") (pintype "passive"))
      (node (ref "R26") (pin "1") (pinfunction "1_1") (pintype "passive"))
    )
    (net (code "7") (name "ADC_CH2") (class "Default")
      (node (ref "IC3") (pin "3") (pinfunction "CH2+_3") (pintype "bidirectional"))
      (node (ref "R31") (pin "1") (pinfunction "1_1") (pintype "passive"))
      (node (ref "R32") (pin "1") (pinfunction "1_1") (pintype "passive"))
    )
    (net (code "8") (name "ADC_CH3") (class "Default")
      (node (ref "IC3") (pin "11") (pinfunction "CH3+_11") (pintype "bidirectional"))
      (node (ref "R33") (pin "1") (pinfunction "1_1") (pintype "passive"))
      (node (ref "R34") (pin "1") (pinfunction "1_1") (pintype "passive"))
    )
    (net (code "9") (name "ADC_CH4") (class "Default")
      (node (ref "IC3") (pin "13") (pinfunction "CH4+_13") (pintype "bidirectional"))
      (node (ref "R35") (pin "1") (pinfunction "1_1") (pintype "passive"))
      (node (ref "R36") (pin "1") (pinfunction "1_1") (pintype "passive"))
    )
    (net (code "10") (name "ALCC") (class "Default")
      (node (ref "IC1") (pin "4") (pinfunction "SENSOR_VP_4") (pintype "bidirectional"))
      (node (ref "J1") (pin "3") (pinfunction "3_3") (pintype "bidirectional"))
      (node (ref "R20") (pin "2") (pinfunction "2_2") (pintype "passive"))
    )
    (net (code "11") (name "BAT+") (class "Default")
      (node (ref "F1") (pin "1") (pinfunction "1_1") (pintype "bidirectional"))
      (node (ref "U$17") (pin "P$1") (pinfunction "P$2_P$1") (pintype "bidirectional"))
      (node (ref "U$17") (pin "P$2") (pinfunction "P$2_P$2") (pintype "bidirectional"))
      (node (ref "U$17") (pin "P$3") (pinfunction "P$2_P$3") (pintype "bidirectional"))
      (node (ref "U$17") (pin "P$4") (pinfunction "P$2_P$4") (pintype "bidirectional"))
    )
    (net (code "12") (name "DHT22_DATA") (class "Default")
      (node (ref "IC1") (pin "31") (pinfunction "IO19_31") (pintype "bidirectional"))
      (node (ref "IC6") (pin "2") (pinfunction "DATA_2") (pintype "bidirectional"))
      (node (ref "R12") (pin "2") (pinfunction "2_2") (pintype "passive"))
    )
    (net (code "13") (name "DISPLAY_BUSY") (class "Default")
      (node (ref "IC1") (pin "26") (pinfunction "IO4_26") (pintype "bidirectional"))
      (node (ref "SV1") (pin "8") (pinfunction "8_8") (pintype "passive"))
      (node (ref "U$1") (pin "BUSY") (pinfunction "BUSY_BUSY") (pintype "bidirectional"))
    )
    (net (code "14") (name "DISPLAY_CLK") (class "Default")
      (node (ref "IC1") (pin "30") (pinfunction "IO18_30") (pintype "bidirectional"))
      (node (ref "SV1") (pin "4") (pinfunction "4_4") (pintype "passive"))
      (node (ref "U$1") (pin "CLK") (pinfunction "CLK_CLK") (pintype "bidirectional"))
    )
    (net (code "15") (name "DISPLAY_CS") (class "Default")
      (node (ref "IC1") (pin "29") (pinfunction "IO5_29") (pintype "bidirectional"))
      (node (ref "SV1") (pin "5") (pinfunction "5_5") (pintype "passive"))
      (node (ref "U$1") (pin "CS") (pinfunction "CS_CS") (pintype "bidirectional"))
    )
    (net (code "16") (name "DISPLAY_DC") (class "Default")
      (node (ref "IC1") (pin "28") (pinfunction "IO17_28") (pintype "bidirectional"))
      (node (ref "SV1") (pin "6") (pinfunction "6_6") (pintype "passive"))
      (node (ref "U$1") (pin "DC") (pinfunction "DC_DC") (pintype "bidirectional"))
    )
    (net (code "17") (name "DISPLAY_DIN") (class "Default")
      (node (ref "IC1") (pin "37") (pinfunction "IO23_37") (pintype "bidirectional"))
      (node (ref "SV1") (pin "3") (pinfunction "3_3") (pintype "passive"))
      (node (ref "U$1") (pin "DIN") (pinfunction "DIN_DIN") (pintype "bidirectional"))
    )
    (net (code "18") (name "DISPLAY_RST") (class "Default")
      (node (ref "IC1") (pin "27") (pinfunction "IO16_27") (pintype "bidirectional"))
      (node (ref "SV1") (pin "7") (pinfunction "7_7") (pintype "passive"))
      (node (ref "U$1") (pin "RST") (pinfunction "RST_RST") (pintype "bidirectional"))
    )
    (net (code "19") (name "DS18B20_DATA") (class "Default")
      (node (ref "IC1") (pin "11") (pinfunction "IO26_11") (pintype "bidirectional"))
      (node (ref "R43") (pin "2") (pinfunction "2_2") (pintype "passive"))
      (node (ref "X7") (pin "2") (pinfunction "KL_2") (pintype "passive"))
    )
    (net (code "20") (name "DTR") (class "Default")
      (node (ref "IC2") (pin "23") (pinfunction "DTR_23") (pintype "bidirectional"))
      (node (ref "Q3") (pin "2") (pinfunction "E_2") (pintype "bidirectional"))
      (node (ref "R10") (pin "1") (pinfunction "1_1") (pintype "passive"))
    )
    (net (code "21") (name "EN") (class "Default")
      (node (ref "IC1") (pin "3") (pinfunction "EN_3") (pintype "bidirectional"))
      (node (ref "Q2") (pin "3") (pinfunction "C_3") (pintype "bidirectional"))
      (node (ref "R15") (pin "1") (pinfunction "1_1") (pintype "passive"))
      (node (ref "R16") (pin "2") (pinfunction "2_2") (pintype "passive"))
    )
    (net (code "22") (name "EXTERN_BUCHSE") (class "Default")
      (node (ref "R32") (pin "2") (pinfunction "2_2") (pintype "passive"))
      (node (ref "U$19") (pin "P$1") (pinfunction "P$2_P$1") (pintype "bidirectional"))
      (node (ref "U$19") (pin "P$2") (pinfunction "P$2_P$2") (pintype "bidirectional"))
      (node (ref "U$19") (pin "P$3") (pinfunction "P$2_P$3") (pintype "bidirectional"))
      (node (ref "U$19") (pin "P$4") (pinfunction "P$2_P$4") (pintype "bidirectional"))
    )
    (net (code "23") (name "FAN_+") (class "Default")
      (node (ref "D5") (pin "1") (pinfunction "K_1") (pintype "bidirectional"))
      (node (ref "K2") (pin "11") (pinfunction "P_11") (pintype "passive"))
      (node (ref "U$24") (pin "P$1") (pinfunction "P$2_P$1") (pintype "bidirectional"))
      (node (ref "U$24") (pin "P$2") (pinfunction "P$2_P$2") (pintype "bidirectional"))
      (node (ref "U$24") (pin "P$3") (pinfunction "P$2_P$3") (pintype "bidirectional"))
      (node (ref "U$24") (pin "P$4") (pinfunction "P$2_P$4") (pintype "bidirectional"))
    )
    (net (code "24") (name "FAN_-") (class "Default")
      (node (ref "D5") (pin "2") (pinfunction "A_2") (pintype "bidirectional"))
      (node (ref "Q13") (pin "2") (pinfunction "D_2") (pintype "bidirectional"))
      (node (ref "U$27") (pin "P$1") (pinfunction "P$2_P$1") (pintype "bidirectional"))
      (node (ref "U$27") (pin "P$2") (pinfunction "P$2_P$2") (pintype "bidirectional"))
      (node (ref "U$27") (pin "P$3") (pinfunction "P$2_P$3") (pintype "bidirectional"))
      (node (ref "U$27") (pin "P$4") (pinfunction "P$2_P$4") (pintype "bidirectional"))
    )
    (net (code "25") (name "FAN_PWM") (class "Default")
      (node (ref "IC7") (pin "12") (pinfunction "LED6_12") (pintype "bidirectional"))
      (node (ref "Q13") (pin "1") (pinfunction "G_1") (pintype "bidirectional"))
      (node (ref "R41") (pin "1") (pinfunction "1_1") (pintype "passive"))
    )
    (net (code "26") (name "GATE_CMD") (class "Default")
      (node (ref "IC4") (pin "1") (pinfunction "1OUT_1") (pintype "bidirectional"))
      (node (ref "Q1") (pin "1") (pinfunction "G_1") (pintype "bidirectional"))
    )
    (net (code "27") (name "GND") (class "Default")
      (node (ref "C1") (pin "2") (pinfunction "2_2") (pintype "passive"))
      (node (ref "C10") (pin "1") (pinfunction "1_1") (pintype "passive"))
      (node (ref "C11") (pin "1") (pinfunction "1_1") (pintype "passive"))
      (node (ref "C12") (pin "1") (pinfunction "1_1") (pintype "passive"))
      (node (ref "C13") (pin "1") (pinfunction "1_1") (pintype "passive"))
      (node (ref "C14") (pin "1") (pinfunction "1_1") (pintype "passive"))
      (node (ref "C15") (pin "1") (pinfunction "1_1") (pintype "passive"))
      (node (ref "C16") (pin "1") (pinfunction "1_1") (pintype "passive"))
      (node (ref "C17") (pin "2") (pinfunction "2_2") (pintype "passive"))
      (node (ref "C2") (pin "-") (pinfunction "-_-") (pintype "passive"))
      (node (ref "C3") (pin "1") (pinfunction "1_1") (pintype "passive"))
      (node (ref "C4") (pin "2") (pinfunction "2_2") (pintype "passive"))
      (node (ref "C5") (pin "1") (pinfunction "1_1") (pintype "passive"))
      (node (ref "C6") (pin "2") (pinfunction "2_2") (pintype "passive"))
      (node (ref "C7") (pin "-") (pinfunction "-_-") (pintype "passive"))
      (node (ref "C8") (pin "2") (pinfunction "2_2") (pintype "passive"))
      (node (ref "C9") (pin "1") (pinfunction "1_1") (pintype "passive"))
      (node (ref "D1") (pin "1") (pinfunction "COMMON_A_1") (pintype "bidirectional"))
      (node (ref "D11") (pin "2") (pinfunction "A_2") (pintype "bidirectional"))
      (node (ref "IC1") (pin "1") (pinfunction "GND_1_1") (pintype "bidirectional"))
      (node (ref "IC1") (pin "15") (pinfunction "GND_2_15") (pintype "bidirectional"))
      (node (ref "IC1") (pin "23") (pinfunction "IO15_23") (pintype "bidirectional"))
      (node (ref "IC1") (pin "38") (pinfunction "GND_3_38") (pintype "bidirectional"))
      (node (ref "IC1") (pin "39") (pinfunction "GND_4_39") (pintype "bidirectional"))
      (node (ref "IC2") (pin "2") (pinfunction "GND_2") (pintype "bidirectional"))
      (node (ref "IC3") (pin "10") (pinfunction "ADR1_10") (pintype "bidirectional"))
      (node (ref "IC3") (pin "12") (pinfunction "CH3-_12") (pintype "bidirectional"))
      (node (ref "IC3") (pin "14") (pinfunction "CH4-_14") (pintype "bidirectional"))
      (node (ref "IC3") (pin "2") (pinfunction "CH1-_2") (pintype "bidirectional"))
      (node (ref "IC3") (pin "4") (pinfunction "CH2-_4") (pintype "bidirectional"))
      (node (ref "IC3") (pin "5") (pinfunction "VSS_5") (pintype "bidirectional"))
      (node (ref "IC3") (pin "9") (pinfunction "ADR0_9") (pintype "bidirectional"))
      (node (ref "IC4") (pin "4") (pinfunction "GND_4") (pintype "bidirectional"))
      (node (ref "IC4") (pin "5") (pinfunction "2IN+_5") (pintype "bidirectional"))
      (node (ref "IC5") (pin "1") (pinfunction "ADJUST/GROUND_1") (pintype "bidirectional"))
      (node (ref "IC6") (pin "4") (pinfunction "GND_4") (pintype "bidirectional"))
      (node (ref "IC7") (pin "1") (pinfunction "A0_1") (pintype "bidirectional"))
      (node (ref "IC7") (pin "14") (pinfunction "VSS_14") (pintype "bidirectional"))
      (node (ref "IC7") (pin "2") (pinfunction "A1_2") (pintype "bidirectional"))
      (node (ref "IC7") (pin "24") (pinfunction "A5_24") (pintype "bidirectional"))
      (node (ref "IC7") (pin "25") (pinfunction "EXTCLK_25") (pintype "bidirectional"))
      (node (ref "IC7") (pin "3") (pinfunction "A2_3") (pintype "bidirectional"))
      (node (ref "IC7") (pin "4") (pinfunction "A3_4") (pintype "bidirectional"))
      (node (ref "IC7") (pin "5") (pinfunction "A4_5") (pintype "bidirectional"))
      (node (ref "J1") (pin "4") (pinfunction "4_4") (pintype "bidirectional"))
      (node (ref "J2") (pin "5") (pinfunction "5_5") (pintype "bidirectional"))
      (node (ref "J3") (pin "5") (pinfunction "5_5") (pintype "bidirectional"))
      (node (ref "LED2") (pin "C") (pinfunction "C_C") (pintype "passive"))
      (node (ref "PS1") (pin "1") (pinfunction "-VIN_1") (pintype "bidirectional"))
      (node (ref "PS1") (pin "10") (pinfunction "-VOUT_10") (pintype "bidirectional"))
      (node (ref "Q10") (pin "3") (pinfunction "S_3") (pintype "bidirectional"))
      (node (ref "Q11") (pin "3") (pinfunction "S_3") (pintype "bidirectional"))
      (node (ref "Q12") (pin "3") (pinfunction "S_3") (pintype "bidirectional"))
      (node (ref "Q13") (pin "3") (pinfunction "S_3") (pintype "bidirectional"))
      (node (ref "Q8") (pin "3") (pinfunction "S_3") (pintype "bidirectional"))
      (node (ref "R1") (pin "2") (pinfunction "2_2") (pintype "passive"))
      (node (ref "R27") (pin "2") (pinfunction "2_2") (pintype "passive"))
      (node (ref "R28") (pin "2") (pinfunction "2_2") (pintype "passive"))
      (node (ref "R29") (pin "2") (pinfunction "2_2") (pintype "passive"))
      (node (ref "R30") (pin "2") (pinfunction "2_2") (pintype "passive"))
      (node (ref "R31") (pin "2") (pinfunction "2_2") (pintype "passive"))
      (node (ref "R33") (pin "2") (pinfunction "2_2") (pintype "passive"))
      (node (ref "R35") (pin "2") (pinfunction "2_2") (pintype "passive"))
      (node (ref "R4") (pin "2") (pinfunction "2_2") (pintype "passive"))
      (node (ref "R40") (pin "1") (pinfunction "1_1") (pintype "passive"))
      (node (ref "R41") (pin "2") (pinfunction "2_2") (pintype "passive"))
      (node (ref "R6") (pin "2") (pinfunction "2_2") (pintype "passive"))
      (node (ref "R8") (pin "2") (pinfunction "2_2") (pintype "passive"))
      (node (ref "S1") (pin "A1") (pinfunction "COM_1_A1") (pintype "bidirectional"))
      (node (ref "S1") (pin "B1") (pinfunction "COM_2_B1") (pintype "bidirectional"))
      (node (ref "S2") (pin "A1") (pinfunction "COM_1_A1") (pintype "bidirectional"))
      (node (ref "S2") (pin "B1") (pinfunction "COM_2_B1") (pintype "bidirectional"))
      (node (ref "SV1") (pin "2") (pinfunction "2_2") (pintype "passive"))
      (node (ref "SV3") (pin "1") (pinfunction "1_1") (pintype "passive"))
      (node (ref "U$1") (pin "GND") (pinfunction "GND_GND") (pintype "bidirectional"))
      (node (ref "U$1") (pin "GND1") (pinfunction "GND_GND1") (pintype "bidirectional"))
      (node (ref "U$1") (pin "GND2") (pinfunction "GND_GND2") (pintype "bidirectional"))
      (node (ref "U$1") (pin "GND3") (pinfunction "GND_GND3") (pintype "bidirectional"))
      (node (ref "U$1") (pin "GND4") (pinfunction "GND_GND4") (pintype "bidirectional"))
      (node (ref "U$1") (pin "GND5") (pinfunction "GND_GND5") (pintype "bidirectional"))
      (node (ref "U$1") (pin "GND6") (pinfunction "GND_GND6") (pintype "bidirectional"))
      (node (ref "U$1") (pin "GND7") (pinfunction "GND_GND7") (pintype "bidirectional"))
      (node (ref "U$12") (pin "CATHODE") (pinfunction "CATHODE_CATHODE") (pintype "bidirectional"))
      (node (ref "U$2") (pin "P$1") (pinfunction "P$2_P$1") (pintype "bidirectional"))
      (node (ref "U$2") (pin "P$2") (pinfunction "P$2_P$2") (pintype "bidirectional"))
      (node (ref "U$2") (pin "P$3") (pinfunction "P$2_P$3") (pintype "bidirectional"))
      (node (ref "U$2") (pin "P$4") (pinfunction "P$2_P$4") (pintype "bidirectional"))
      (node (ref "X1") (pin "5") (pinfunction "5_5") (pintype "input"))
      (node (ref "X4") (pin "2") (pinfunction "KL_2") (pintype "passive"))
      (node (ref "X7") (pin "1") (pinfunction "KL_1") (pintype "passive"))
    )
    (net (code "28") (name "IO0") (class "Default")
      (node (ref "IC1") (pin "25") (pinfunction "IO0_25") (pintype "bidirectional"))
      (node (ref "Q3") (pin "3") (pinfunction "C_3") (pintype "bidirectional"))
      (node (ref "R14") (pin "1") (pinfunction "1_1") (pintype "passive"))
      (node (ref "R17") (pin "2") (pinfunction "2_2") (pintype "passive"))
    )
    (net (code "29") (name "IO2") (class "Default")
      (node (ref "IC1") (pin "24") (pinfunction "IO2_24") (pintype "bidirectional"))
      (node (ref "R18") (pin "1") (pinfunction "1_1") (pintype "passive"))
    )
    (net (code "30") (name "LADEN_BUCHSE") (class "Default")
      (node (ref "D6") (pin "1") (pinfunction "K_1") (pintype "bidirectional"))
      (node (ref "K2") (pin "14") (pinfunction "S_14") (pintype "passive"))
      (node (ref "R26") (pin "2") (pinfunction "2_2") (pintype "passive"))
      (node (ref "U$18") (pin "P$1") (pinfunction "P$2_P$1") (pintype "bidirectional"))
      (node (ref "U$18") (pin "P$2") (pinfunction "P$2_P$2") (pintype "bidirectional"))
      (node (ref "U$18") (pin "P$3") (pinfunction "P$2_P$3") (pintype "bidirectional"))
      (node (ref "U$18") (pin "P$4") (pinfunction "P$2_P$4") (pintype "bidirectional"))
      (node (ref "U$21") (pin "P$1") (pinfunction "P$2_P$1") (pintype "bidirectional"))
      (node (ref "U$21") (pin "P$2") (pinfunction "P$2_P$2") (pintype "bidirectional"))
      (node (ref "U$21") (pin "P$3") (pinfunction "P$2_P$3") (pintype "bidirectional"))
      (node (ref "U$21") (pin "P$4") (pinfunction "P$2_P$4") (pintype "bidirectional"))
    )
    (net (code "31") (name "MOSFET_PC_REMOTE") (class "Default")
      (node (ref "IC7") (pin "13") (pinfunction "LED7_13") (pintype "bidirectional"))
      (node (ref "Q10") (pin "1") (pinfunction "G_1") (pintype "bidirectional"))
      (node (ref "R28") (pin "1") (pinfunction "1_1") (pintype "passive"))
    )
    (net (code "32") (name "Net-(D3-A)") (class "Default")
      (node (ref "D3") (pin "2") (pinfunction "A_2") (pintype "bidirectional"))
      (node (ref "K2") (pin "A2") (pinfunction "2_A2") (pintype "passive"))
      (node (ref "Q8") (pin "2") (pinfunction "D_2") (pintype "bidirectional"))
    )
    (net (code "33") (name "Net-(D6-A)") (class "Default")
      (node (ref "D6") (pin "2") (pinfunction "A_2") (pintype "bidirectional"))
      (node (ref "Q11") (pin "2") (pinfunction "D_2") (pintype "bidirectional"))
      (node (ref "U$20") (pin "P$1") (pinfunction "P$2_P$1") (pintype "bidirectional"))
      (node (ref "U$20") (pin "P$2") (pinfunction "P$2_P$2") (pintype "bidirectional"))
      (node (ref "U$20") (pin "P$3") (pinfunction "P$2_P$3") (pintype "bidirectional"))
      (node (ref "U$20") (pin "P$4") (pinfunction "P$2_P$4") (pintype "bidirectional"))
    )
    (net (code "34") (name "Net-(D10-A)") (class "Default")
      (node (ref "D10") (pin "2") (pinfunction "A_2") (pintype "bidirectional"))
      (node (ref "Q12") (pin "2") (pinfunction "D_2") (pintype "bidirectional"))
      (node (ref "U$22") (pin "P$1") (pinfunction "P$2_P$1") (pintype "bidirectional"))
      (node (ref "U$22") (pin "P$2") (pinfunction "P$2_P$2") (pintype "bidirectional"))
      (node (ref "U$22") (pin "P$3") (pinfunction "P$2_P$3") (pintype "bidirectional"))
      (node (ref "U$22") (pin "P$4") (pinfunction "P$2_P$4") (pintype "bidirectional"))
    )
    (net (code "35") (name "Net-(IC2-TXD)") (class "Default")
      (node (ref "IC2") (pin "21") (pinfunction "TXD_21") (pintype "bidirectional"))
      (node (ref "R11") (pin "1") (pinfunction "1_1") (pintype "passive"))
    )
    (net (code "36") (name "Net-(IC2-VBUS)") (class "Default")
      (node (ref "IC2") (pin "8") (pinfunction "VBUS_8") (pintype "bidirectional"))
      (node (ref "R7") (pin "1") (pinfunction "1_1") (pintype "passive"))
      (node (ref "R8") (pin "1") (pinfunction "1_1") (pintype "passive"))
    )
    (net (code "37") (name "Net-(IC2-VPP)") (class "Default")
      (node (ref "C16") (pin "2") (pinfunction "2_2") (pintype "passive"))
      (node (ref "IC2") (pin "16") (pinfunction "VPP_16") (pintype "bidirectional"))
    )
    (net (code "38") (name "Net-(IC2-~{RST})") (class "Default")
      (node (ref "IC2") (pin "9") (pinfunction "~{RST}_9") (pintype "bidirectional"))
      (node (ref "R9") (pin "1") (pinfunction "1_1") (pintype "passive"))
    )
    (net (code "39") (name "Net-(IC4-2IN-)") (class "Default")
      (node (ref "IC4") (pin "6") (pinfunction "2IN-_6") (pintype "bidirectional"))
      (node (ref "IC4") (pin "7") (pinfunction "2OUT_7") (pintype "bidirectional"))
    )
    (net (code "40") (name "Net-(IC7-LED0)") (class "Default")
      (node (ref "IC7") (pin "6") (pinfunction "LED0_6") (pintype "bidirectional"))
      (node (ref "R37") (pin "1") (pinfunction "1_1") (pintype "passive"))
    )
    (net (code "41") (name "Net-(IC7-LED1)") (class "Default")
      (node (ref "IC7") (pin "7") (pinfunction "LED1_7") (pintype "bidirectional"))
      (node (ref "R38") (pin "1") (pinfunction "1_1") (pintype "passive"))
    )
    (net (code "42") (name "Net-(IC7-LED2)") (class "Default")
      (node (ref "IC7") (pin "8") (pinfunction "LED2_8") (pintype "bidirectional"))
      (node (ref "R39") (pin "1") (pinfunction "1_1") (pintype "passive"))
    )
    (net (code "43") (name "Net-(IC7-~{OE})") (class "Default")
      (node (ref "IC7") (pin "23") (pinfunction "~{OE}_23") (pintype "bidirectional"))
      (node (ref "R40") (pin "2") (pinfunction "2_2") (pintype "passive"))
    )
    (net (code "44") (name "Net-(LED2-PadA)") (class "Default")
      (node (ref "LED2") (pin "A") (pinfunction "A_A") (pintype "passive"))
      (node (ref "R18") (pin "2") (pinfunction "2_2") (pintype "passive"))
    )
    (net (code "45") (name "Net-(Q2-B)") (class "Default")
      (node (ref "Q2") (pin "1") (pinfunction "B_1") (pintype "bidirectional"))
      (node (ref "R10") (pin "2") (pinfunction "2_2") (pintype "passive"))
    )
    (net (code "46") (name "Net-(Q3-B)") (class "Default")
      (node (ref "Q3") (pin "1") (pinfunction "B_1") (pintype "bidirectional"))
      (node (ref "R2") (pin "1") (pinfunction "1_1") (pintype "passive"))
    )
    (net (code "47") (name "Net-(R37-Pad2)") (class "Default")
      (node (ref "R37") (pin "2") (pinfunction "2_2") (pintype "passive"))
      (node (ref "U$12") (pin "ANODE_BLUE") (pinfunction "ANODE_BLUE_ANODE_BLUE") (pintype "bidirectional"))
    )
    (net (code "48") (name "Net-(R38-Pad2)") (class "Default")
      (node (ref "R38") (pin "2") (pinfunction "2_2") (pintype "passive"))
      (node (ref "U$12") (pin "ANODE_RED") (pinfunction "ANODE_RED_ANODE_RED") (pintype "bidirectional"))
    )
    (net (code "49") (name "Net-(R39-Pad2)") (class "Default")
      (node (ref "R39") (pin "2") (pinfunction "2_2") (pintype "passive"))
      (node (ref "U$12") (pin "ANODE_GREEN") (pinfunction "ANODE_GREEN_ANODE_GREEN") (pintype "bidirectional"))
    )
    (net (code "50") (name "Net-(S1-NO_2)") (class "Default")
      (node (ref "R15") (pin "2") (pinfunction "2_2") (pintype "passive"))
      (node (ref "S1") (pin "D1") (pinfunction "NO_2_D1") (pintype "bidirectional"))
    )
    (net (code "51") (name "Net-(S2-NO_2)") (class "Default")
      (node (ref "R14") (pin "2") (pinfunction "2_2") (pintype "passive"))
      (node (ref "S2") (pin "D1") (pinfunction "NO_2_D1") (pintype "bidirectional"))
    )
    (net (code "52") (name "OPAMP-NEG") (class "Default")
      (node (ref "IC4") (pin "2") (pinfunction "1IN-_2") (pintype "bidirectional"))
      (node (ref "R5") (pin "2") (pinfunction "2_2") (pintype "passive"))
      (node (ref "R6") (pin "1") (pinfunction "1_1") (pintype "passive"))
    )
    (net (code "53") (name "OPAMP-POS") (class "Default")
      (node (ref "IC4") (pin "3") (pinfunction "1IN+_3") (pintype "bidirectional"))
      (node (ref "R3") (pin "2") (pinfunction "2_2") (pintype "passive"))
      (node (ref "R4") (pin "1") (pinfunction "1_1") (pintype "passive"))
    )
    (net (code "54") (name "PC_REMOTE_ANSCHLUSS") (class "Default")
      (node (ref "Q10") (pin "2") (pinfunction "D_2") (pintype "bidirectional"))
      (node (ref "U$25") (pin "P$1") (pinfunction "P$2_P$1") (pintype "bidirectional"))
      (node (ref "U$25") (pin "P$2") (pinfunction "P$2_P$2") (pintype "bidirectional"))
      (node (ref "U$25") (pin "P$3") (pinfunction "P$2_P$3") (pintype "bidirectional"))
      (node (ref "U$25") (pin "P$4") (pinfunction "P$2_P$4") (pintype "bidirectional"))
    )
    (net (code "55") (name "PC_REMOTE_LED") (class "Default")
      (node (ref "R42") (pin "1") (pinfunction "1_1") (pintype "passive"))
      (node (ref "U$28") (pin "P$1") (pinfunction "P$2_P$1") (pintype "bidirectional"))
      (node (ref "U$28") (pin "P$2") (pinfunction "P$2_P$2") (pintype "bidirectional"))
      (node (ref "U$28") (pin "P$3") (pinfunction "P$2_P$3") (pintype "bidirectional"))
      (node (ref "U$28") (pin "P$4") (pinfunction "P$2_P$4") (pintype "bidirectional"))
    )
    (net (code "56") (name "PC_REMOTE_LED_3V3") (class "Default")
      (node (ref "D11") (pin "1") (pinfunction "K_1") (pintype "bidirectional"))
      (node (ref "IC1") (pin "12") (pinfunction "IO27_12") (pintype "bidirectional"))
      (node (ref "R42") (pin "2") (pinfunction "2_2") (pintype "passive"))
    )
    (net (code "57") (name "RELAIS_FAN") (class "Default")
      (node (ref "IC7") (pin "9") (pinfunction "LED3_9") (pintype "bidirectional"))
      (node (ref "Q8") (pin "1") (pinfunction "G_1") (pintype "bidirectional"))
      (node (ref "R27") (pin "1") (pinfunction "1_1") (pintype "passive"))
    )
    (net (code "58") (name "RELAIS_R1_R2") (class "Default")
      (node (ref "IC7") (pin "11") (pinfunction "LED5_11") (pintype "bidirectional"))
      (node (ref "Q11") (pin "1") (pinfunction "G_1") (pintype "bidirectional"))
      (node (ref "R29") (pin "1") (pinfunction "1_1") (pintype "passive"))
    )
    (net (code "59") (name "RELAIS_R3") (class "Default")
      (node (ref "IC7") (pin "10") (pinfunction "LED4_10") (pintype "bidirectional"))
      (node (ref "Q12") (pin "1") (pinfunction "G_1") (pintype "bidirectional"))
      (node (ref "R30") (pin "1") (pinfunction "1_1") (pintype "passive"))
    )
    (net (code "60") (name "ROT_CLK") (class "Default")
      (node (ref "IC1") (pin "14") (pinfunction "IO12_14") (pintype "bidirectional"))
      (node (ref "SV3") (pin "5") (pinfunction "5_5") (pintype "passive"))
    )
    (net (code "61") (name "ROT_DT") (class "Default")
      (node (ref "IC1") (pin "16") (pinfunction "IO13_16") (pintype "bidirectional"))
      (node (ref "SV3") (pin "4") (pinfunction "4_4") (pintype "passive"))
    )
    (net (code "62") (name "ROT_SW") (class "Default")
      (node (ref "IC1") (pin "13") (pinfunction "IO14_13") (pintype "bidirectional"))
      (node (ref "SV3") (pin "3") (pinfunction "3_3") (pintype "passive"))
    )
    (net (code "63") (name "RTS") (class "Default")
      (node (ref "IC2") (pin "19") (pinfunction "RTS_19") (pintype "bidirectional"))
      (node (ref "Q2") (pin "2") (pinfunction "E_2") (pintype "bidirectional"))
      (node (ref "R2") (pin "2") (pinfunction "2_2") (pintype "passive"))
    )
    (net (code "64") (name "SCL") (class "Default")
      (node (ref "IC1") (pin "36") (pinfunction "IO22_36") (pintype "bidirectional"))
      (node (ref "IC3") (pin "8") (pinfunction "SCL_8") (pintype "bidirectional"))
      (node (ref "IC7") (pin "26") (pinfunction "SCL_26") (pintype "bidirectional"))
      (node (ref "J1") (pin "1") (pinfunction "1_1") (pintype "bidirectional"))
      (node (ref "J2") (pin "1") (pinfunction "1_1") (pintype "bidirectional"))
      (node (ref "J3") (pin "1") (pinfunction "1_1") (pintype "bidirectional"))
      (node (ref "R13") (pin "2") (pinfunction "2_2") (pintype "passive"))
    )
    (net (code "65") (name "SDA") (class "Default")
      (node (ref "IC1") (pin "33") (pinfunction "IO21_33") (pintype "bidirectional"))
      (node (ref "IC3") (pin "7") (pinfunction "SDA_7") (pintype "bidirectional"))
      (node (ref "IC7") (pin "27") (pinfunction "SDA_27") (pintype "bidirectional"))
      (node (ref "J1") (pin "2") (pinfunction "2_2") (pintype "bidirectional"))
      (node (ref "J2") (pin "2") (pinfunction "2_2") (pintype "bidirectional"))
      (node (ref "J3") (pin "2") (pinfunction "2_2") (pintype "bidirectional"))
      (node (ref "R19") (pin "2") (pinfunction "2_2") (pintype "passive"))
    )
    (net (code "66") (name "SYSTEM") (class "Default")
      (node (ref "K2") (pin "12") (pinfunction "O_12") (pintype "passive"))
      (node (ref "U$26") (pin "P$1") (pinfunction "P$2_P$1") (pintype "bidirectional"))
      (node (ref "U$26") (pin "P$2") (pinfunction "P$2_P$2") (pintype "bidirectional"))
      (node (ref "U$26") (pin "P$3") (pinfunction "P$2_P$3") (pintype "bidirectional"))
      (node (ref "U$26") (pin "P$4") (pinfunction "P$2_P$4") (pintype "bidirectional"))
    )
    (net (code "67") (name "TASTER_1") (class "Default")
      (node (ref "IC1") (pin "6") (pinfunction "IO34_6") (pintype "bidirectional"))
      (node (ref "R21") (pin "1") (pinfunction "1_1") (pintype "passive"))
      (node (ref "X2") (pin "1") (pinfunction "KL_1") (pintype "passive"))
    )
    (net (code "68") (name "TASTER_2") (class "Default")
      (node (ref "IC1") (pin "7") (pinfunction "IO35_7") (pintype "bidirectional"))
      (node (ref "R22") (pin "1") (pinfunction "1_1") (pintype "passive"))
      (node (ref "X2") (pin "2") (pinfunction "KL_2") (pintype "passive"))
    )
    (net (code "69") (name "TASTER_3") (class "Default")
      (node (ref "IC1") (pin "8") (pinfunction "IO32_8") (pintype "bidirectional"))
      (node (ref "R23") (pin "1") (pinfunction "1_1") (pintype "passive"))
      (node (ref "X3") (pin "1") (pinfunction "KL_1") (pintype "passive"))
    )
    (net (code "70") (name "TASTER_4") (class "Default")
      (node (ref "IC1") (pin "9") (pinfunction "IO33_9") (pintype "bidirectional"))
      (node (ref "R24") (pin "1") (pinfunction "1_1") (pintype "passive"))
      (node (ref "X3") (pin "2") (pinfunction "KL_2") (pintype "passive"))
    )
    (net (code "71") (name "TASTER_5") (class "Default")
      (node (ref "IC1") (pin "10") (pinfunction "IO25_10") (pintype "bidirectional"))
      (node (ref "R25") (pin "1") (pinfunction "1_1") (pintype "passive"))
      (node (ref "X4") (pin "1") (pinfunction "KL_1") (pintype "passive"))
    )
    (net (code "72") (name "UART_ESP_RXD0") (class "Default")
      (node (ref "IC1") (pin "34") (pinfunction "RXD0_34") (pintype "bidirectional"))
      (node (ref "R11") (pin "2") (pinfunction "2_2") (pintype "passive"))
    )
    (net (code "73") (name "UART_ESP_TXD0") (class "Default")
      (node (ref "IC1") (pin "35") (pinfunction "TXD0_35") (pintype "bidirectional"))
      (node (ref "IC2") (pin "20") (pinfunction "RXD_20") (pintype "bidirectional"))
    )
    (net (code "74") (name "USBVCC") (class "Default")
      (node (ref "D1") (pin "2") (pinfunction "K_1_2") (pintype "bidirectional"))
      (node (ref "Q1") (pin "2") (pinfunction "S_2") (pintype "bidirectional"))
      (node (ref "R7") (pin "2") (pinfunction "2_2") (pintype "passive"))
      (node (ref "X1") (pin "1") (pinfunction "1_1") (pintype "input"))
    )
    (net (code "75") (name "USB_DN") (class "Default")
      (node (ref "D1") (pin "4") (pinfunction "K_3_4") (pintype "bidirectional"))
      (node (ref "IC2") (pin "4") (pinfunction "D-_4") (pintype "bidirectional"))
      (node (ref "X1") (pin "2") (pinfunction "2_2") (pintype "input"))
    )
    (net (code "76") (name "USB_DP") (class "Default")
      (node (ref "D1") (pin "3") (pinfunction "K_2_3") (pintype "bidirectional"))
      (node (ref "IC2") (pin "3") (pinfunction "D+_3") (pintype "bidirectional"))
      (node (ref "X1") (pin "3") (pinfunction "3_3") (pintype "input"))
    )
    (net (code "77") (name "VCC") (class "Default")
      (node (ref "C2") (pin "+") (pinfunction "+_+") (pintype "passive"))
      (node (ref "C3") (pin "2") (pinfunction "2_2") (pintype "passive"))
      (node (ref "D10") (pin "1") (pinfunction "K_1") (pintype "bidirectional"))
      (node (ref "F1") (pin "2") (pinfunction "2_2") (pintype "bidirectional"))
      (node (ref "PS1") (pin "16") (pinfunction "+VIN_16") (pintype "bidirectional"))
      (node (ref "R3") (pin "1") (pinfunction "1_1") (pintype "passive"))
      (node (ref "U$23") (pin "P$1") (pinfunction "P$2_P$1") (pintype "bidirectional"))
      (node (ref "U$23") (pin "P$2") (pinfunction "P$2_P$2") (pintype "bidirectional"))
      (node (ref "U$23") (pin "P$3") (pinfunction "P$2_P$3") (pintype "bidirectional"))
      (node (ref "U$23") (pin "P$4") (pinfunction "P$2_P$4") (pintype "bidirectional"))
    )
    (net (code "78") (name "unconnected-(IC1-NC-Pad32)") (class "Default")
      (node (ref "IC1") (pin "32") (pinfunction "NC_32") (pintype "no_connect"))
    )
    (net (code "79") (name "unconnected-(IC1-SCK{slash}CLK-Pad20)") (class "Default")
      (node (ref "IC1") (pin "20") (pinfunction "SCK/CLK_20") (pintype "bidirectional"))
    )
    (net (code "80") (name "unconnected-(IC1-SCS{slash}CMD-Pad19)") (class "Default")
      (node (ref "IC1") (pin "19") (pinfunction "SCS/CMD_19") (pintype "bidirectional"))
    )
    (net (code "81") (name "unconnected-(IC1-SDI{slash}SD1-Pad22)") (class "Default")
      (node (ref "IC1") (pin "22") (pinfunction "SDI/SD1_22") (pintype "bidirectional"))
    )
    (net (code "82") (name "unconnected-(IC1-SDO{slash}SD0-Pad21)") (class "Default")
      (node (ref "IC1") (pin "21") (pinfunction "SDO/SD0_21") (pintype "bidirectional"))
    )
    (net (code "83") (name "unconnected-(IC1-SENSOR_VN-Pad5)") (class "Default")
      (node (ref "IC1") (pin "5") (pinfunction "SENSOR_VN_5") (pintype "bidirectional"))
    )
    (net (code "84") (name "unconnected-(IC1-SHD{slash}SD2-Pad17)") (class "Default")
      (node (ref "IC1") (pin "17") (pinfunction "SHD/SD2_17") (pintype "bidirectional"))
    )
    (net (code "85") (name "unconnected-(IC1-SWP{slash}SD3-Pad18)") (class "Default")
      (node (ref "IC1") (pin "18") (pinfunction "SWP/SD3_18") (pintype "bidirectional"))
    )
    (net (code "86") (name "unconnected-(IC2-CTS-Pad18)") (class "Default")
      (node (ref "IC2") (pin "18") (pinfunction "CTS_18") (pintype "bidirectional"))
    )
    (net (code "87") (name "unconnected-(IC2-DCD-Pad24)") (class "Default")
      (node (ref "IC2") (pin "24") (pinfunction "DCD_24") (pintype "bidirectional"))
    )
    (net (code "88") (name "unconnected-(IC2-DSR-Pad22)") (class "Default")
      (node (ref "IC2") (pin "22") (pinfunction "DSR_22") (pintype "bidirectional"))
    )
    (net (code "89") (name "unconnected-(IC2-EP-Pad25)") (class "Default")
      (node (ref "IC2") (pin "25") (pinfunction "EP_25") (pintype "bidirectional"))
    )
    (net (code "90") (name "unconnected-(IC2-GPIO.0-Pad14)") (class "Default")
      (node (ref "IC2") (pin "14") (pinfunction "GPIO.0_14") (pintype "bidirectional"))
    )
    (net (code "91") (name "unconnected-(IC2-GPIO.1-Pad13)") (class "Default")
      (node (ref "IC2") (pin "13") (pinfunction "GPIO.1_13") (pintype "bidirectional"))
    )
    (net (code "92") (name "unconnected-(IC2-GPIO.2-Pad12)") (class "Default")
      (node (ref "IC2") (pin "12") (pinfunction "GPIO.2_12") (pintype "bidirectional"))
    )
    (net (code "93") (name "unconnected-(IC2-GPIO.3-Pad11)") (class "Default")
      (node (ref "IC2") (pin "11") (pinfunction "GPIO.3_11") (pintype "bidirectional"))
    )
    (net (code "94") (name "unconnected-(IC2-NC-Pad10)") (class "Default")
      (node (ref "IC2") (pin "10") (pinfunction "NC_10") (pintype "no_connect"))
    )
    (net (code "95") (name "unconnected-(IC2-RI-Pad1)") (class "Default")
      (node (ref "IC2") (pin "1") (pinfunction "RI_1") (pintype "bidirectional"))
    )
    (net (code "96") (name "unconnected-(IC2-SUSPEND-Pad17)") (class "Default")
      (node (ref "IC2") (pin "17") (pinfunction "SUSPEND_17") (pintype "bidirectional"))
    )
    (net (code "97") (name "unconnected-(IC2-~{SUSPEND}-Pad15)") (class "Default")
      (node (ref "IC2") (pin "15") (pinfunction "~{SUSPEND}_15") (pintype "bidirectional"))
    )
    (net (code "98") (name "unconnected-(IC6-NULL-Pad3)") (class "Default")
      (node (ref "IC6") (pin "3") (pinfunction "NULL_3") (pintype "bidirectional"))
    )
    (net (code "99") (name "unconnected-(IC7-LED8-Pad15)") (class "Default")
      (node (ref "IC7") (pin "15") (pinfunction "LED8_15") (pintype "bidirectional"))
    )
    (net (code "100") (name "unconnected-(IC7-LED9-Pad16)") (class "Default")
      (node (ref "IC7") (pin "16") (pinfunction "LED9_16") (pintype "bidirectional"))
    )
    (net (code "101") (name "unconnected-(IC7-LED10-Pad17)") (class "Default")
      (node (ref "IC7") (pin "17") (pinfunction "LED10_17") (pintype "bidirectional"))
    )
    (net (code "102") (name "unconnected-(IC7-LED11-Pad18)") (class "Default")
      (node (ref "IC7") (pin "18") (pinfunction "LED11_18") (pintype "bidirectional"))
    )
    (net (code "103") (name "unconnected-(IC7-LED12-Pad19)") (class "Default")
      (node (ref "IC7") (pin "19") (pinfunction "LED12_19") (pintype "bidirectional"))
    )
    (net (code "104") (name "unconnected-(IC7-LED13-Pad20)") (class "Default")
      (node (ref "IC7") (pin "20") (pinfunction "LED13_20") (pintype "bidirectional"))
    )
    (net (code "105") (name "unconnected-(IC7-LED14-Pad21)") (class "Default")
      (node (ref "IC7") (pin "21") (pinfunction "LED14_21") (pintype "bidirectional"))
    )
    (net (code "106") (name "unconnected-(IC7-LED15-Pad22)") (class "Default")
      (node (ref "IC7") (pin "22") (pinfunction "LED15_22") (pintype "bidirectional"))
    )
    (net (code "107") (name "unconnected-(PS1-N.C._1-Pad7)") (class "Default")
      (node (ref "PS1") (pin "7") (pinfunction "N.C._1_7") (pintype "bidirectional"))
    )
    (net (code "108") (name "unconnected-(PS1-N.C._2-Pad8)") (class "Default")
      (node (ref "PS1") (pin "8") (pinfunction "N.C._2_8") (pintype "bidirectional"))
    )
    (net (code "109") (name "unconnected-(S1-NO_1-PadC1)") (class "Default")
      (node (ref "S1") (pin "C1") (pinfunction "NO_1_C1") (pintype "bidirectional"))
    )
    (net (code "110") (name "unconnected-(S2-NO_1-PadC1)") (class "Default")
      (node (ref "S2") (pin "C1") (pinfunction "NO_1_C1") (pintype "bidirectional"))
    )
    (net (code "111") (name "unconnected-(X1-Pad4)") (class "Default")
      (node (ref "X1") (pin "4") (pinfunction "4_4") (pintype "input"))
    )
  )
)
